# FPGA-1.net
KiCad netlist of a schematic drawn in Altium Designer
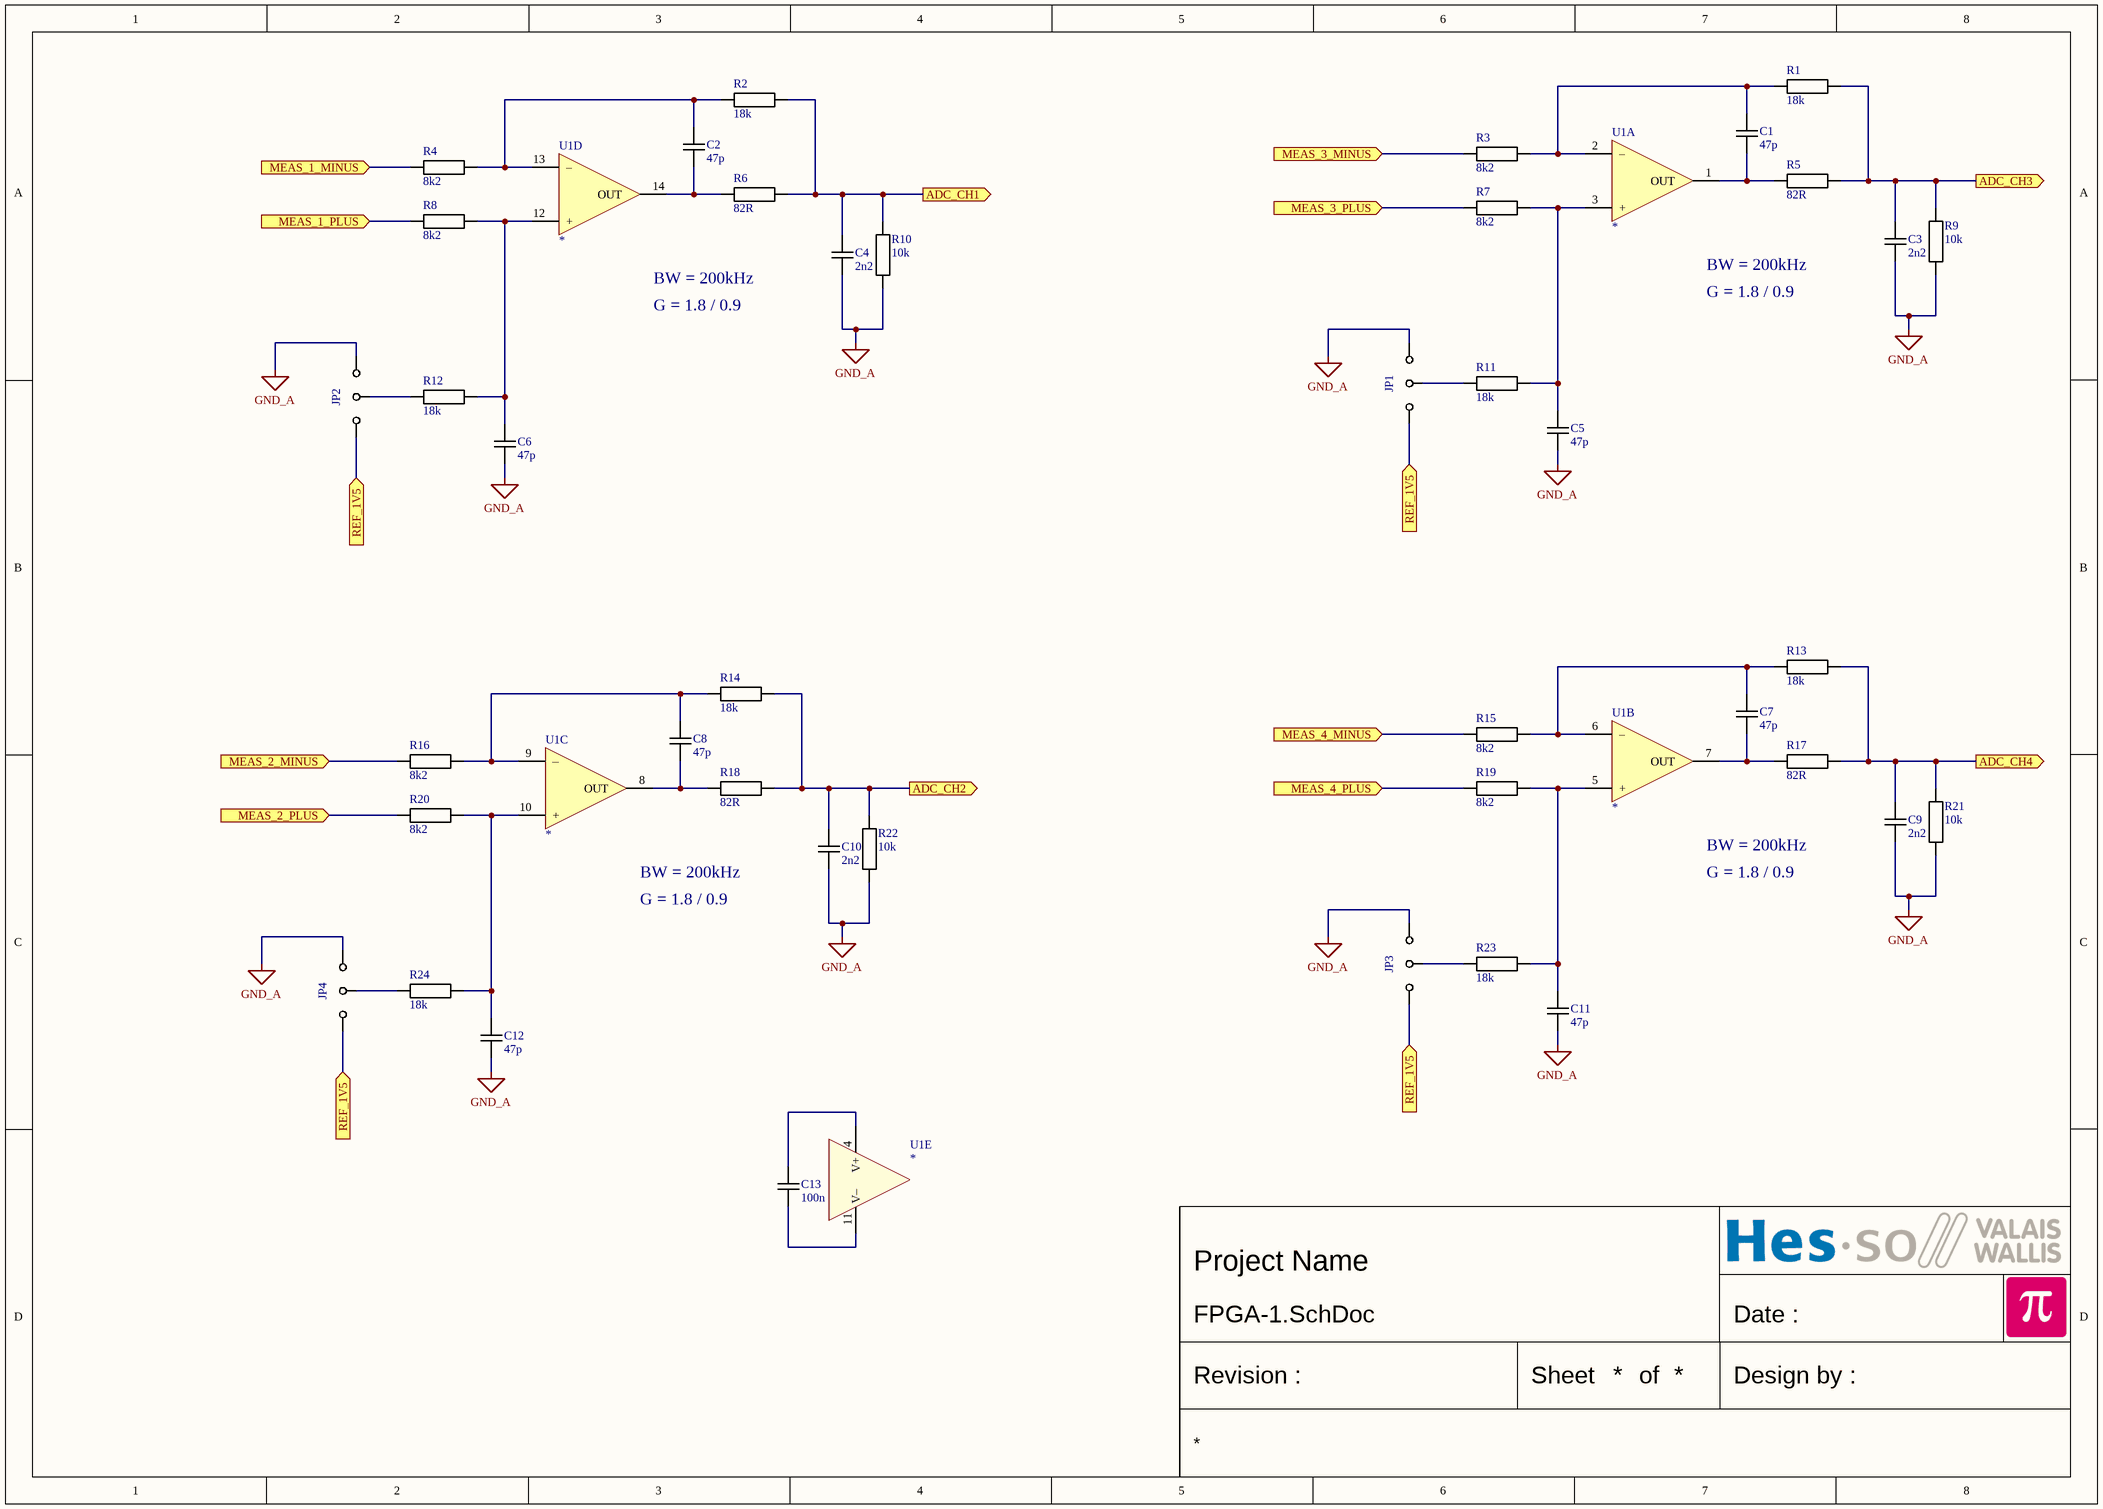
[diagram p0: FPGA-1.SchDoc]

(export (version "E")
  (design (tool "Eeschema 10.0.6"))
  (components
    (comp (ref "C1")
      (value "47p")
      (footprint "CAPACITOR 1608 REFLOW")
      (description "Capacitor X7R 10% 50V 1608(0603)")
      (libsource (lib "Capacitor") (part "Capacitor"))
    )
    (comp (ref "C2")
      (value "47p")
      (footprint "CAPACITOR 1608 REFLOW")
      (description "Capacitor X7R 10% 50V 1608(0603)")
      (libsource (lib "Capacitor") (part "Capacitor"))
    )
    (comp (ref "C3")
      (value "2n2")
      (footprint "CAPACITOR 1608 REFLOW")
      (description "Capacitor X7R 10% 50V 1608(0603)")
      (libsource (lib "Capacitor") (part "Capacitor"))
    )
    (comp (ref "C4")
      (value "2n2")
      (footprint "CAPACITOR 1608 REFLOW")
      (description "Capacitor X7R 10% 50V 1608(0603)")
      (libsource (lib "Capacitor") (part "Capacitor"))
    )
    (comp (ref "C5")
      (value "47p")
      (footprint "CAPACITOR 1608 REFLOW")
      (description "Capacitor X7R 10% 50V 1608(0603)")
      (libsource (lib "Capacitor") (part "Capacitor"))
    )
    (comp (ref "C6")
      (value "47p")
      (footprint "CAPACITOR 1608 REFLOW")
      (description "Capacitor X7R 10% 50V 1608(0603)")
      (libsource (lib "Capacitor") (part "Capacitor"))
    )
    (comp (ref "C7")
      (value "47p")
      (footprint "CAPACITOR 1608 REFLOW")
      (description "Capacitor X7R 10% 50V 1608(0603)")
      (libsource (lib "Capacitor") (part "Capacitor"))
    )
    (comp (ref "C8")
      (value "47p")
      (footprint "CAPACITOR 1608 REFLOW")
      (description "Capacitor X7R 10% 50V 1608(0603)")
      (libsource (lib "Capacitor") (part "Capacitor"))
    )
    (comp (ref "C9")
      (value "2n2")
      (footprint "CAPACITOR 1608 REFLOW")
      (description "Capacitor X7R 10% 50V 1608(0603)")
      (libsource (lib "Capacitor") (part "Capacitor"))
    )
    (comp (ref "C10")
      (value "2n2")
      (footprint "CAPACITOR 1608 REFLOW")
      (description "Capacitor X7R 10% 50V 1608(0603)")
      (libsource (lib "Capacitor") (part "Capacitor"))
    )
    (comp (ref "C11")
      (value "47p")
      (footprint "CAPACITOR 1608 REFLOW")
      (description "Capacitor X7R 10% 50V 1608(0603)")
      (libsource (lib "Capacitor") (part "Capacitor"))
    )
    (comp (ref "C12")
      (value "47p")
      (footprint "CAPACITOR 1608 REFLOW")
      (description "Capacitor X7R 10% 50V 1608(0603)")
      (libsource (lib "Capacitor") (part "Capacitor"))
    )
    (comp (ref "C13")
      (value "100n")
      (footprint "CAPACITOR 1608 REFLOW")
      (description "Capacitor X7R 10% 50V 1608(0603)")
      (libsource (lib "Capacitor") (part "Capacitor"))
    )
    (comp (ref "JP1")
      (value "{Value}")
      (footprint "JUMPER3 SMD 1608")
      (description "JUMPER 3 POS")
      (libsource (lib "Jumper") (part "JUMPER 3 POS"))
    )
    (comp (ref "JP2")
      (value "{Value}")
      (footprint "JUMPER3 SMD 1608")
      (description "JUMPER 3 POS")
      (libsource (lib "Jumper") (part "JUMPER 3 POS"))
    )
    (comp (ref "JP3")
      (value "{Value}")
      (footprint "JUMPER3 SMD 1608")
      (description "JUMPER 3 POS")
      (libsource (lib "Jumper") (part "JUMPER 3 POS"))
    )
    (comp (ref "JP4")
      (value "{Value}")
      (footprint "JUMPER3 SMD 1608")
      (description "JUMPER 3 POS")
      (libsource (lib "Jumper") (part "JUMPER 3 POS"))
    )
    (comp (ref "R1")
      (value "18k")
      (footprint "RESISTOR 1608 REFLOW")
      (description "Resistor 1% 50V 100mW 1608(0603)")
      (libsource (lib "Resistor") (part "Resistor"))
    )
    (comp (ref "R2")
      (value "18k")
      (footprint "RESISTOR 1608 REFLOW")
      (description "Resistor 1% 50V 100mW 1608(0603)")
      (libsource (lib "Resistor") (part "Resistor"))
    )
    (comp (ref "R3")
      (value "8k2")
      (footprint "RESISTOR 1608 REFLOW")
      (description "Resistor 1% 50V 100mW 1608(0603)")
      (libsource (lib "Resistor") (part "Resistor"))
    )
    (comp (ref "R4")
      (value "8k2")
      (footprint "RESISTOR 1608 REFLOW")
      (description "Resistor 1% 50V 100mW 1608(0603)")
      (libsource (lib "Resistor") (part "Resistor"))
    )
    (comp (ref "R5")
      (value "82R")
      (footprint "RESISTOR 1608 REFLOW")
      (description "Resistor 1% 50V 100mW 1608(0603)")
      (libsource (lib "Resistor") (part "Resistor"))
    )
    (comp (ref "R6")
      (value "82R")
      (footprint "RESISTOR 1608 REFLOW")
      (description "Resistor 1% 50V 100mW 1608(0603)")
      (libsource (lib "Resistor") (part "Resistor"))
    )
    (comp (ref "R7")
      (value "8k2")
      (footprint "RESISTOR 1608 REFLOW")
      (description "Resistor 1% 50V 100mW 1608(0603)")
      (libsource (lib "Resistor") (part "Resistor"))
    )
    (comp (ref "R8")
      (value "8k2")
      (footprint "RESISTOR 1608 REFLOW")
      (description "Resistor 1% 50V 100mW 1608(0603)")
      (libsource (lib "Resistor") (part "Resistor"))
    )
    (comp (ref "R9")
      (value "10k")
      (footprint "RESISTOR 1608 REFLOW")
      (description "Resistor 1% 50V 100mW 1608(0603)")
      (libsource (lib "Resistor") (part "Resistor"))
    )
    (comp (ref "R10")
      (value "10k")
      (footprint "RESISTOR 1608 REFLOW")
      (description "Resistor 1% 50V 100mW 1608(0603)")
      (libsource (lib "Resistor") (part "Resistor"))
    )
    (comp (ref "R11")
      (value "18k")
      (footprint "RESISTOR 1608 REFLOW")
      (description "Resistor 1% 50V 100mW 1608(0603)")
      (libsource (lib "Resistor") (part "Resistor"))
    )
    (comp (ref "R12")
      (value "18k")
      (footprint "RESISTOR 1608 REFLOW")
      (description "Resistor 1% 50V 100mW 1608(0603)")
      (libsource (lib "Resistor") (part "Resistor"))
    )
    (comp (ref "R13")
      (value "18k")
      (footprint "RESISTOR 1608 REFLOW")
      (description "Resistor 1% 50V 100mW 1608(0603)")
      (libsource (lib "Resistor") (part "Resistor"))
    )
    (comp (ref "R14")
      (value "18k")
      (footprint "RESISTOR 1608 REFLOW")
      (description "Resistor 1% 50V 100mW 1608(0603)")
      (libsource (lib "Resistor") (part "Resistor"))
    )
    (comp (ref "R15")
      (value "8k2")
      (footprint "RESISTOR 1608 REFLOW")
      (description "Resistor 1% 50V 100mW 1608(0603)")
      (libsource (lib "Resistor") (part "Resistor"))
    )
    (comp (ref "R16")
      (value "8k2")
      (footprint "RESISTOR 1608 REFLOW")
      (description "Resistor 1% 50V 100mW 1608(0603)")
      (libsource (lib "Resistor") (part "Resistor"))
    )
    (comp (ref "R17")
      (value "82R")
      (footprint "RESISTOR 1608 REFLOW")
      (description "Resistor 1% 50V 100mW 1608(0603)")
      (libsource (lib "Resistor") (part "Resistor"))
    )
    (comp (ref "R18")
      (value "82R")
      (footprint "RESISTOR 1608 REFLOW")
      (description "Resistor 1% 50V 100mW 1608(0603)")
      (libsource (lib "Resistor") (part "Resistor"))
    )
    (comp (ref "R19")
      (value "8k2")
      (footprint "RESISTOR 1608 REFLOW")
      (description "Resistor 1% 50V 100mW 1608(0603)")
      (libsource (lib "Resistor") (part "Resistor"))
    )
    (comp (ref "R20")
      (value "8k2")
      (footprint "RESISTOR 1608 REFLOW")
      (description "Resistor 1% 50V 100mW 1608(0603)")
      (libsource (lib "Resistor") (part "Resistor"))
    )
    (comp (ref "R21")
      (value "10k")
      (footprint "RESISTOR 1608 REFLOW")
      (description "Resistor 1% 50V 100mW 1608(0603)")
      (libsource (lib "Resistor") (part "Resistor"))
    )
    (comp (ref "R22")
      (value "10k")
      (footprint "RESISTOR 1608 REFLOW")
      (description "Resistor 1% 50V 100mW 1608(0603)")
      (libsource (lib "Resistor") (part "Resistor"))
    )
    (comp (ref "R23")
      (value "18k")
      (footprint "RESISTOR 1608 REFLOW")
      (description "Resistor 1% 50V 100mW 1608(0603)")
      (libsource (lib "Resistor") (part "Resistor"))
    )
    (comp (ref "R24")
      (value "18k")
      (footprint "RESISTOR 1608 REFLOW")
      (description "Resistor 1% 50V 100mW 1608(0603)")
      (libsource (lib "Resistor") (part "Resistor"))
    )
    (comp (ref "U1")
      (value "*")
      (footprint "SO14 P1.27 C4.0X8.8 H1.75")
      (description "Generic quad OPA 14 pins")
      (libsource (lib "Amplifier") (part "OPA QUAD"))
    )
  )
  (nets
    (net (code "1") (name "/ADC_CH1") (class "Default")
      (node (ref "C4") (pin "2") (pinfunction "2_2") (pintype "passive"))
      (node (ref "R10") (pin "1") (pinfunction "1_1") (pintype "passive"))
      (node (ref "R2") (pin "2") (pinfunction "2_2") (pintype "passive"))
      (node (ref "R6") (pin "2") (pinfunction "2_2") (pintype "passive"))
    )
    (net (code "2") (name "/ADC_CH2") (class "Default")
      (node (ref "C10") (pin "2") (pinfunction "2_2") (pintype "passive"))
      (node (ref "R14") (pin "2") (pinfunction "2_2") (pintype "passive"))
      (node (ref "R18") (pin "2") (pinfunction "2_2") (pintype "passive"))
      (node (ref "R22") (pin "1") (pinfunction "1_1") (pintype "passive"))
    )
    (net (code "3") (name "/ADC_CH3") (class "Default")
      (node (ref "C3") (pin "2") (pinfunction "2_2") (pintype "passive"))
      (node (ref "R1") (pin "2") (pinfunction "2_2") (pintype "passive"))
      (node (ref "R5") (pin "2") (pinfunction "2_2") (pintype "passive"))
      (node (ref "R9") (pin "1") (pinfunction "1_1") (pintype "passive"))
    )
    (net (code "4") (name "/ADC_CH4") (class "Default")
      (node (ref "C9") (pin "2") (pinfunction "2_2") (pintype "passive"))
      (node (ref "R13") (pin "2") (pinfunction "2_2") (pintype "passive"))
      (node (ref "R17") (pin "2") (pinfunction "2_2") (pintype "passive"))
      (node (ref "R21") (pin "1") (pinfunction "1_1") (pintype "passive"))
    )
    (net (code "5") (name "/MEAS_1_MINUS") (class "Default")
      (node (ref "R4") (pin "1") (pinfunction "1_1") (pintype "passive"))
    )
    (net (code "6") (name "/MEAS_1_PLUS") (class "Default")
      (node (ref "R8") (pin "1") (pinfunction "1_1") (pintype "passive"))
    )
    (net (code "7") (name "/MEAS_2_MINUS") (class "Default")
      (node (ref "R16") (pin "1") (pinfunction "1_1") (pintype "passive"))
    )
    (net (code "8") (name "/MEAS_2_PLUS") (class "Default")
      (node (ref "R20") (pin "1") (pinfunction "1_1") (pintype "passive"))
    )
    (net (code "9") (name "/MEAS_3_MINUS") (class "Default")
      (node (ref "R3") (pin "1") (pinfunction "1_1") (pintype "passive"))
    )
    (net (code "10") (name "/MEAS_3_PLUS") (class "Default")
      (node (ref "R7") (pin "1") (pinfunction "1_1") (pintype "passive"))
    )
    (net (code "11") (name "/MEAS_4_MINUS") (class "Default")
      (node (ref "R15") (pin "1") (pinfunction "1_1") (pintype "passive"))
    )
    (net (code "12") (name "/MEAS_4_PLUS") (class "Default")
      (node (ref "R19") (pin "1") (pinfunction "1_1") (pintype "passive"))
    )
    (net (code "13") (name "/REF_1V5") (class "Default")
      (node (ref "JP1") (pin "1") (pinfunction "1_1") (pintype "passive"))
      (node (ref "JP2") (pin "1") (pinfunction "1_1") (pintype "passive"))
      (node (ref "JP3") (pin "1") (pinfunction "1_1") (pintype "passive"))
      (node (ref "JP4") (pin "1") (pinfunction "1_1") (pintype "passive"))
    )
    (net (code "14") (name "GND_A") (class "Default")
      (node (ref "C10") (pin "1") (pinfunction "1_1") (pintype "passive"))
      (node (ref "C11") (pin "1") (pinfunction "1_1") (pintype "passive"))
      (node (ref "C12") (pin "1") (pinfunction "1_1") (pintype "passive"))
      (node (ref "C3") (pin "1") (pinfunction "1_1") (pintype "passive"))
      (node (ref "C4") (pin "1") (pinfunction "1_1") (pintype "passive"))
      (node (ref "C5") (pin "1") (pinfunction "1_1") (pintype "passive"))
      (node (ref "C6") (pin "1") (pinfunction "1_1") (pintype "passive"))
      (node (ref "C9") (pin "1") (pinfunction "1_1") (pintype "passive"))
      (node (ref "JP1") (pin "3") (pinfunction "3_3") (pintype "passive"))
      (node (ref "JP2") (pin "3") (pinfunction "3_3") (pintype "passive"))
      (node (ref "JP3") (pin "3") (pinfunction "3_3") (pintype "passive"))
      (node (ref "JP4") (pin "3") (pinfunction "3_3") (pintype "passive"))
      (node (ref "R10") (pin "2") (pinfunction "2_2") (pintype "passive"))
      (node (ref "R21") (pin "2") (pinfunction "2_2") (pintype "passive"))
      (node (ref "R22") (pin "2") (pinfunction "2_2") (pintype "passive"))
      (node (ref "R9") (pin "2") (pinfunction "2_2") (pintype "passive"))
    )
    (net (code "15") (name "Net-(JP1-Pad2)") (class "Default")
      (node (ref "JP1") (pin "2") (pinfunction "2_2") (pintype "passive"))
      (node (ref "R11") (pin "2") (pinfunction "2_2") (pintype "passive"))
    )
    (net (code "16") (name "Net-(JP2-Pad2)") (class "Default")
      (node (ref "JP2") (pin "2") (pinfunction "2_2") (pintype "passive"))
      (node (ref "R12") (pin "2") (pinfunction "2_2") (pintype "passive"))
    )
    (net (code "17") (name "Net-(JP3-Pad2)") (class "Default")
      (node (ref "JP3") (pin "2") (pinfunction "2_2") (pintype "passive"))
      (node (ref "R23") (pin "2") (pinfunction "2_2") (pintype "passive"))
    )
    (net (code "18") (name "Net-(JP4-Pad2)") (class "Default")
      (node (ref "JP4") (pin "2") (pinfunction "2_2") (pintype "passive"))
      (node (ref "R24") (pin "2") (pinfunction "2_2") (pintype "passive"))
    )
    (net (code "19") (name "Net-(U1A-+)") (class "Default")
      (node (ref "C5") (pin "2") (pinfunction "2_2") (pintype "passive"))
      (node (ref "R11") (pin "1") (pinfunction "1_1") (pintype "passive"))
      (node (ref "R7") (pin "2") (pinfunction "2_2") (pintype "passive"))
      (node (ref "U1") (pin "3") (pinfunction "+_3") (pintype "passive"))
    )
    (net (code "20") (name "Net-(U1A-OUT)") (class "Default")
      (node (ref "C1") (pin "1") (pinfunction "1_1") (pintype "passive"))
      (node (ref "R5") (pin "1") (pinfunction "1_1") (pintype "passive"))
      (node (ref "U1") (pin "1") (pinfunction "OUT_1") (pintype "passive"))
    )
    (net (code "21") (name "Net-(U1A-–)") (class "Default")
      (node (ref "C1") (pin "2") (pinfunction "2_2") (pintype "passive"))
      (node (ref "R1") (pin "1") (pinfunction "1_1") (pintype "passive"))
      (node (ref "R3") (pin "2") (pinfunction "2_2") (pintype "passive"))
      (node (ref "U1") (pin "2") (pinfunction "–_2") (pintype "passive"))
    )
    (net (code "22") (name "Net-(U1B-+)") (class "Default")
      (node (ref "C11") (pin "2") (pinfunction "2_2") (pintype "passive"))
      (node (ref "R19") (pin "2") (pinfunction "2_2") (pintype "passive"))
      (node (ref "R23") (pin "1") (pinfunction "1_1") (pintype "passive"))
      (node (ref "U1") (pin "5") (pinfunction "+_5") (pintype "passive"))
    )
    (net (code "23") (name "Net-(U1B-OUT)") (class "Default")
      (node (ref "C7") (pin "1") (pinfunction "1_1") (pintype "passive"))
      (node (ref "R17") (pin "1") (pinfunction "1_1") (pintype "passive"))
      (node (ref "U1") (pin "7") (pinfunction "OUT_7") (pintype "passive"))
    )
    (net (code "24") (name "Net-(U1B-–)") (class "Default")
      (node (ref "C7") (pin "2") (pinfunction "2_2") (pintype "passive"))
      (node (ref "R13") (pin "1") (pinfunction "1_1") (pintype "passive"))
      (node (ref "R15") (pin "2") (pinfunction "2_2") (pintype "passive"))
      (node (ref "U1") (pin "6") (pinfunction "–_6") (pintype "passive"))
    )
    (net (code "25") (name "Net-(U1C-+)") (class "Default")
      (node (ref "C12") (pin "2") (pinfunction "2_2") (pintype "passive"))
      (node (ref "R20") (pin "2") (pinfunction "2_2") (pintype "passive"))
      (node (ref "R24") (pin "1") (pinfunction "1_1") (pintype "passive"))
      (node (ref "U1") (pin "10") (pinfunction "+_10") (pintype "passive"))
    )
    (net (code "26") (name "Net-(U1C-OUT)") (class "Default")
      (node (ref "C8") (pin "1") (pinfunction "1_1") (pintype "passive"))
      (node (ref "R18") (pin "1") (pinfunction "1_1") (pintype "passive"))
      (node (ref "U1") (pin "8") (pinfunction "OUT_8") (pintype "passive"))
    )
    (net (code "27") (name "Net-(U1C-–)") (class "Default")
      (node (ref "C8") (pin "2") (pinfunction "2_2") (pintype "passive"))
      (node (ref "R14") (pin "1") (pinfunction "1_1") (pintype "passive"))
      (node (ref "R16") (pin "2") (pinfunction "2_2") (pintype "passive"))
      (node (ref "U1") (pin "9") (pinfunction "–_9") (pintype "passive"))
    )
    (net (code "28") (name "Net-(U1D-+)") (class "Default")
      (node (ref "C6") (pin "2") (pinfunction "2_2") (pintype "passive"))
      (node (ref "R12") (pin "1") (pinfunction "1_1") (pintype "passive"))
      (node (ref "R8") (pin "2") (pinfunction "2_2") (pintype "passive"))
      (node (ref "U1") (pin "12") (pinfunction "+_12") (pintype "passive"))
    )
    (net (code "29") (name "Net-(U1D-OUT)") (class "Default")
      (node (ref "C2") (pin "1") (pinfunction "1_1") (pintype "passive"))
      (node (ref "R6") (pin "1") (pinfunction "1_1") (pintype "passive"))
      (node (ref "U1") (pin "14") (pinfunction "OUT_14") (pintype "passive"))
    )
    (net (code "30") (name "Net-(U1D-–)") (class "Default")
      (node (ref "C2") (pin "2") (pinfunction "2_2") (pintype "passive"))
      (node (ref "R2") (pin "1") (pinfunction "1_1") (pintype "passive"))
      (node (ref "R4") (pin "2") (pinfunction "2_2") (pintype "passive"))
      (node (ref "U1") (pin "13") (pinfunction "–_13") (pintype "passive"))
    )
    (net (code "31") (name "Net-(U1E-V+)") (class "Default")
      (node (ref "C13") (pin "2") (pinfunction "2_2") (pintype "passive"))
      (node (ref "U1") (pin "4") (pinfunction "V+_4") (pintype "passive"))
    )
    (net (code "32") (name "Net-(U1E-V–)") (class "Default")
      (node (ref "C13") (pin "1") (pinfunction "1_1") (pintype "passive"))
      (node (ref "U1") (pin "11") (pinfunction "V–_11") (pintype "passive"))
    )
  )
)
